# stoomshield1.net
KiCad netlist of a schematic drawn in EAGLE
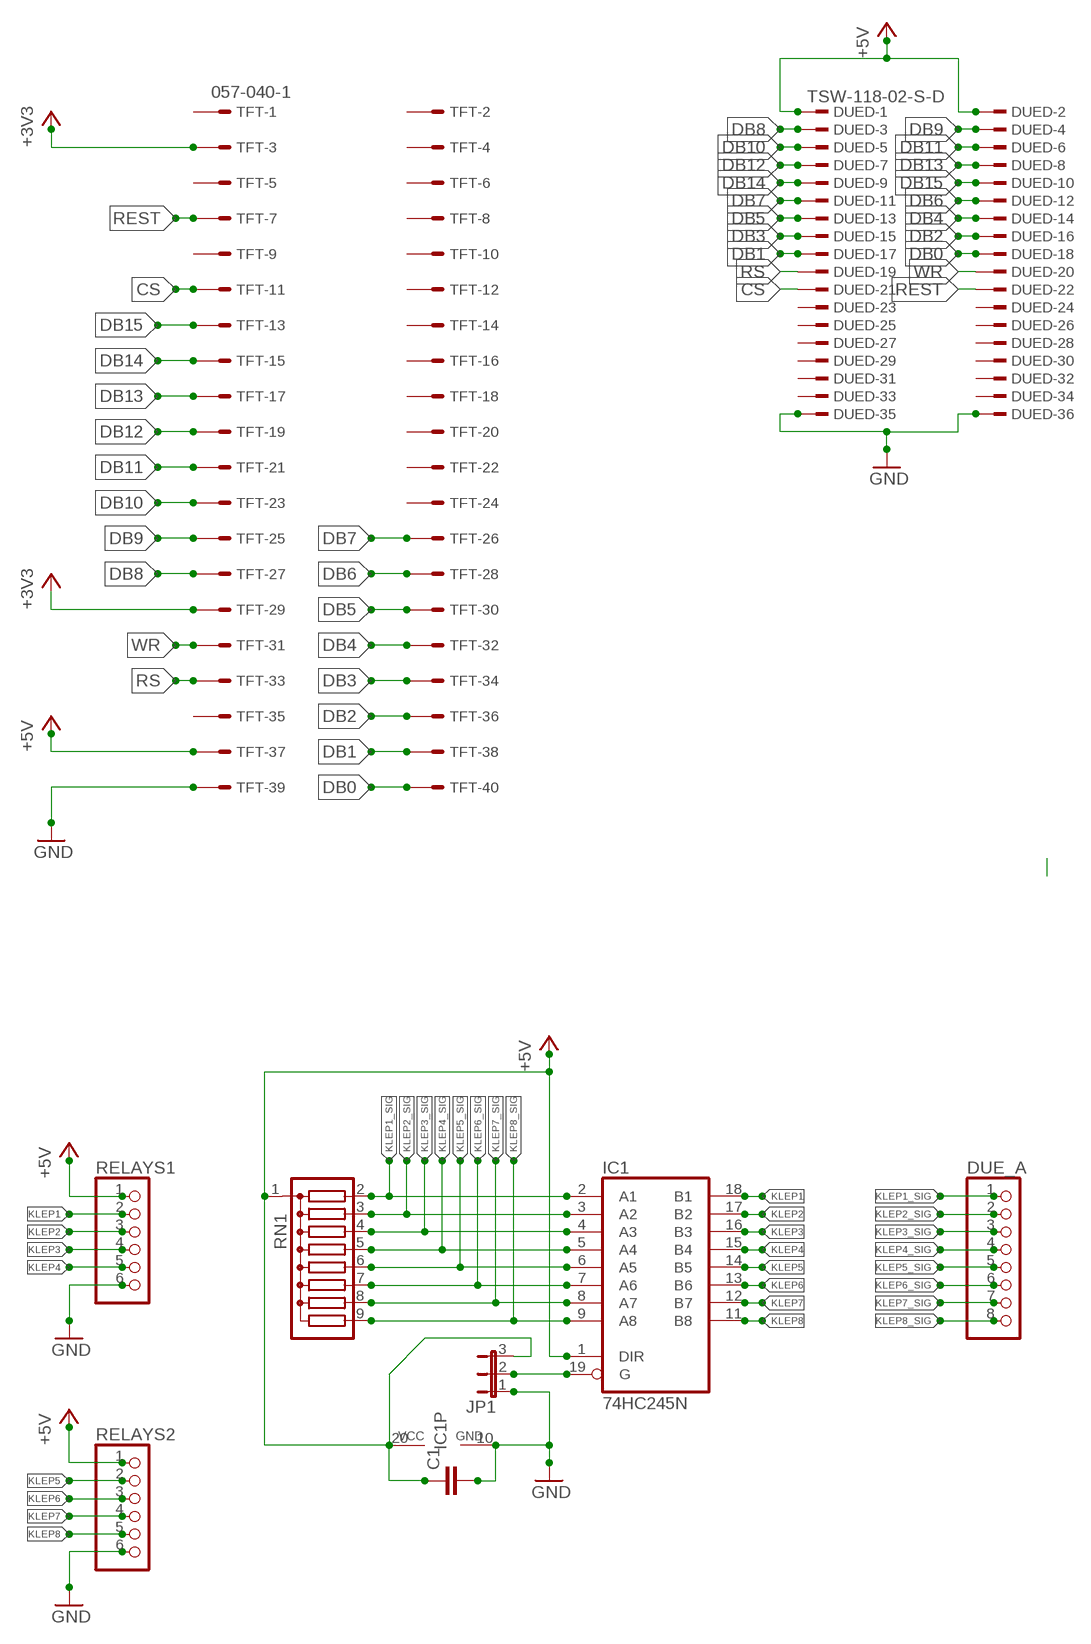
[diagram p0: schematic, sheet 1, part 1 of 2]
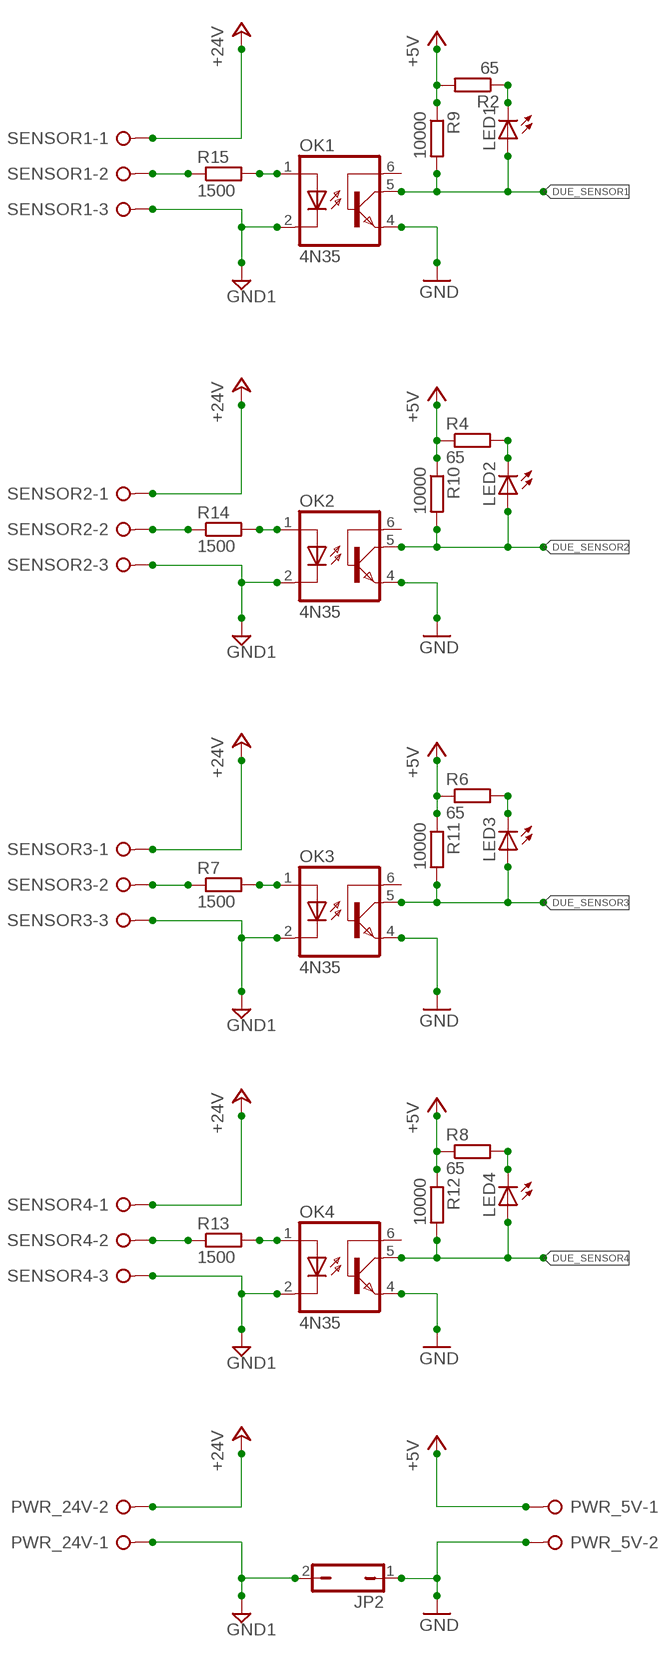
[diagram p1: schematic, sheet 1, part 2 of 2]

(export (version "E")
  (design (tool "Eeschema 10.0.6"))
  (components
    (comp (ref "C1")
      (value "C-EU025-024X044")
      (footprint "eagle-import:C025-024X044")
      (libsource (lib "eagle-import") (part "C-EU025-024X044"))
    )
    (comp (ref "DUED")
      (value "TSW-118-02-S-D")
      (footprint "eagle-import:TSW-118-02-S-D")
      (libsource (lib "eagle-import") (part "TSW-118-02-S-D"))
    )
    (comp (ref "DUE_A")
      (value "PINHD-1X8")
      (footprint "eagle-import:1X08")
      (libsource (lib "eagle-import") (part "PINHD-1X8"))
    )
    (comp (ref "IC1")
      (value "74HC245N")
      (footprint "eagle-import:DIL20")
      (libsource (lib "eagle-import") (part "74245NHC"))
    )
    (comp (ref "JP1")
      (value "JP2E")
      (footprint "eagle-import:JP2")
      (libsource (lib "eagle-import") (part "JP2E"))
    )
    (comp (ref "JP2")
      (value "JP1Q")
      (footprint "eagle-import:JP1")
      (libsource (lib "eagle-import") (part "JP1Q"))
    )
    (comp (ref "LED1")
      (value "LED5MM")
      (footprint "eagle-import:LED5MM")
      (libsource (lib "eagle-import") (part "LED5MM"))
    )
    (comp (ref "LED2")
      (value "LED5MM")
      (footprint "eagle-import:LED5MM")
      (libsource (lib "eagle-import") (part "LED5MM"))
    )
    (comp (ref "LED3")
      (value "LED5MM")
      (footprint "eagle-import:LED5MM")
      (libsource (lib "eagle-import") (part "LED5MM"))
    )
    (comp (ref "LED4")
      (value "LED5MM")
      (footprint "eagle-import:LED5MM")
      (libsource (lib "eagle-import") (part "LED5MM"))
    )
    (comp (ref "OK1")
      (value "4N35")
      (footprint "eagle-import:DIL06")
      (fields (field (name "MF") "FAIRCHILD SEMICONDUCTOR"))
      (libsource (lib "eagle-import") (part "4N35"))
    )
    (comp (ref "OK2")
      (value "4N35")
      (footprint "eagle-import:DIL06")
      (fields (field (name "MF") "FAIRCHILD SEMICONDUCTOR"))
      (libsource (lib "eagle-import") (part "4N35"))
    )
    (comp (ref "OK3")
      (value "4N35")
      (footprint "eagle-import:DIL06")
      (fields (field (name "MF") "FAIRCHILD SEMICONDUCTOR"))
      (libsource (lib "eagle-import") (part "4N35"))
    )
    (comp (ref "OK4")
      (value "4N35")
      (footprint "eagle-import:DIL06")
      (fields (field (name "MF") "FAIRCHILD SEMICONDUCTOR"))
      (libsource (lib "eagle-import") (part "4N35"))
    )
    (comp (ref "PWR_5V")
      (value "W237-02P")
      (footprint "eagle-import:W237-132")
      (libsource (lib "eagle-import") (part "W237-02P"))
    )
    (comp (ref "PWR_24V")
      (value "W237-02P")
      (footprint "eagle-import:W237-132")
      (libsource (lib "eagle-import") (part "W237-02P"))
    )
    (comp (ref "R2")
      (value "65")
      (footprint "eagle-import:0204_5")
      (libsource (lib "eagle-import") (part "R-EU_0204/5"))
    )
    (comp (ref "R4")
      (value "65")
      (footprint "eagle-import:0204_5")
      (libsource (lib "eagle-import") (part "R-EU_0204/5"))
    )
    (comp (ref "R6")
      (value "65")
      (footprint "eagle-import:0204_5")
      (libsource (lib "eagle-import") (part "R-EU_0204/5"))
    )
    (comp (ref "R7")
      (value "1500")
      (footprint "eagle-import:0204_5")
      (libsource (lib "eagle-import") (part "R-EU_0204/5"))
    )
    (comp (ref "R8")
      (value "65")
      (footprint "eagle-import:0204_5")
      (libsource (lib "eagle-import") (part "R-EU_0204/5"))
    )
    (comp (ref "R9")
      (value "10000")
      (footprint "eagle-import:0204_5")
      (libsource (lib "eagle-import") (part "R-EU_0204/5"))
    )
    (comp (ref "R10")
      (value "10000")
      (footprint "eagle-import:0204_5")
      (libsource (lib "eagle-import") (part "R-EU_0204/5"))
    )
    (comp (ref "R11")
      (value "10000")
      (footprint "eagle-import:0204_5")
      (libsource (lib "eagle-import") (part "R-EU_0204/5"))
    )
    (comp (ref "R12")
      (value "10000")
      (footprint "eagle-import:0204_5")
      (libsource (lib "eagle-import") (part "R-EU_0204/5"))
    )
    (comp (ref "R13")
      (value "1500")
      (footprint "eagle-import:0204_5")
      (libsource (lib "eagle-import") (part "R-EU_0204/5"))
    )
    (comp (ref "R14")
      (value "1500")
      (footprint "eagle-import:0204_5")
      (libsource (lib "eagle-import") (part "R-EU_0204/5"))
    )
    (comp (ref "R15")
      (value "1500")
      (footprint "eagle-import:0204_5")
      (libsource (lib "eagle-import") (part "R-EU_0204/5"))
    )
    (comp (ref "RELAYS1")
      (value "PINHD-1X6")
      (footprint "eagle-import:1X06")
      (libsource (lib "eagle-import") (part "PINHD-1X6"))
    )
    (comp (ref "RELAYS2")
      (value "PINHD-1X6")
      (footprint "eagle-import:1X06")
      (libsource (lib "eagle-import") (part "PINHD-1X6"))
    )
    (comp (ref "RN1")
      (value "G08R")
      (footprint "eagle-import:SIL9")
      (libsource (lib "eagle-import") (part "G08R"))
    )
    (comp (ref "SENSOR1")
      (value "W237-03P")
      (footprint "eagle-import:W237-133")
      (libsource (lib "eagle-import") (part "W237-03P"))
    )
    (comp (ref "SENSOR2")
      (value "W237-03P")
      (footprint "eagle-import:W237-133")
      (libsource (lib "eagle-import") (part "W237-03P"))
    )
    (comp (ref "SENSOR3")
      (value "W237-03P")
      (footprint "eagle-import:W237-133")
      (libsource (lib "eagle-import") (part "W237-03P"))
    )
    (comp (ref "SENSOR4")
      (value "W237-03P")
      (footprint "eagle-import:W237-133")
      (libsource (lib "eagle-import") (part "W237-03P"))
    )
    (comp (ref "TFT")
      (value "057-040-1")
      (footprint "eagle-import:057-040-1")
      (libsource (lib "eagle-import") (part "057-040-1"))
    )
  )
  (nets
    (net (code "1") (name "+3V3") (class "Default")
      (node (ref "TFT") (pin "29") (pinfunction "S_29") (pintype "passive"))
      (node (ref "TFT") (pin "3") (pinfunction "S_3") (pintype "passive"))
    )
    (net (code "2") (name "+5V") (class "Default")
      (node (ref "C1") (pin "1") (pinfunction "1_1") (pintype "passive"))
      (node (ref "DUED") (pin "1") (pinfunction "1_1") (pintype "passive"))
      (node (ref "DUED") (pin "2") (pinfunction "1_2") (pintype "passive"))
      (node (ref "IC1") (pin "1") (pinfunction "DIR_1") (pintype "input"))
      (node (ref "IC1") (pin "20") (pinfunction "VCC_20") (pintype "power_in"))
      (node (ref "JP1") (pin "3") (pinfunction "3_3") (pintype "passive"))
      (node (ref "PWR_5V") (pin "1") (pinfunction "KL_1") (pintype "passive"))
      (node (ref "R10") (pin "1") (pinfunction "1_1") (pintype "passive"))
      (node (ref "R11") (pin "1") (pinfunction "1_1") (pintype "passive"))
      (node (ref "R12") (pin "1") (pinfunction "1_1") (pintype "passive"))
      (node (ref "R2") (pin "2") (pinfunction "2_2") (pintype "passive"))
      (node (ref "R4") (pin "1") (pinfunction "1_1") (pintype "passive"))
      (node (ref "R6") (pin "1") (pinfunction "1_1") (pintype "passive"))
      (node (ref "R8") (pin "1") (pinfunction "1_1") (pintype "passive"))
      (node (ref "R9") (pin "1") (pinfunction "1_1") (pintype "passive"))
      (node (ref "RELAYS1") (pin "1") (pinfunction "1_1") (pintype "passive"))
      (node (ref "RELAYS2") (pin "1") (pinfunction "1_1") (pintype "passive"))
      (node (ref "RN1") (pin "1") (pinfunction "1_1") (pintype "passive"))
      (node (ref "TFT") (pin "37") (pinfunction "S_37") (pintype "passive"))
    )
    (net (code "3") (name "+24V") (class "Default")
      (node (ref "PWR_24V") (pin "2") (pinfunction "KL_2") (pintype "passive"))
      (node (ref "SENSOR1") (pin "1") (pinfunction "KL_1") (pintype "passive"))
      (node (ref "SENSOR2") (pin "1") (pinfunction "KL_1") (pintype "passive"))
      (node (ref "SENSOR3") (pin "1") (pinfunction "KL_1") (pintype "passive"))
      (node (ref "SENSOR4") (pin "1") (pinfunction "KL_1") (pintype "passive"))
    )
    (net (code "4") (name "CS") (class "Default")
      (node (ref "DUED") (pin "21") (pinfunction "1_21") (pintype "passive"))
      (node (ref "TFT") (pin "11") (pinfunction "S_11") (pintype "passive"))
    )
    (net (code "5") (name "DB0") (class "Default")
      (node (ref "DUED") (pin "18") (pinfunction "1_18") (pintype "passive"))
      (node (ref "TFT") (pin "40") (pinfunction "S_40") (pintype "passive"))
    )
    (net (code "6") (name "DB1") (class "Default")
      (node (ref "DUED") (pin "17") (pinfunction "1_17") (pintype "passive"))
      (node (ref "TFT") (pin "38") (pinfunction "S_38") (pintype "passive"))
    )
    (net (code "7") (name "DB2") (class "Default")
      (node (ref "DUED") (pin "16") (pinfunction "1_16") (pintype "passive"))
      (node (ref "TFT") (pin "36") (pinfunction "S_36") (pintype "passive"))
    )
    (net (code "8") (name "DB3") (class "Default")
      (node (ref "DUED") (pin "15") (pinfunction "1_15") (pintype "passive"))
      (node (ref "TFT") (pin "34") (pinfunction "S_34") (pintype "passive"))
    )
    (net (code "9") (name "DB4") (class "Default")
      (node (ref "DUED") (pin "14") (pinfunction "1_14") (pintype "passive"))
      (node (ref "TFT") (pin "32") (pinfunction "S_32") (pintype "passive"))
    )
    (net (code "10") (name "DB5") (class "Default")
      (node (ref "DUED") (pin "13") (pinfunction "1_13") (pintype "passive"))
      (node (ref "TFT") (pin "30") (pinfunction "S_30") (pintype "passive"))
    )
    (net (code "11") (name "DB6") (class "Default")
      (node (ref "DUED") (pin "12") (pinfunction "1_12") (pintype "passive"))
      (node (ref "TFT") (pin "28") (pinfunction "S_28") (pintype "passive"))
    )
    (net (code "12") (name "DB7") (class "Default")
      (node (ref "DUED") (pin "11") (pinfunction "1_11") (pintype "passive"))
      (node (ref "TFT") (pin "26") (pinfunction "S_26") (pintype "passive"))
    )
    (net (code "13") (name "DB8") (class "Default")
      (node (ref "DUED") (pin "3") (pinfunction "1_3") (pintype "passive"))
      (node (ref "TFT") (pin "27") (pinfunction "S_27") (pintype "passive"))
    )
    (net (code "14") (name "DB9") (class "Default")
      (node (ref "DUED") (pin "4") (pinfunction "1_4") (pintype "passive"))
      (node (ref "TFT") (pin "25") (pinfunction "S_25") (pintype "passive"))
    )
    (net (code "15") (name "DB10") (class "Default")
      (node (ref "DUED") (pin "5") (pinfunction "1_5") (pintype "passive"))
      (node (ref "TFT") (pin "23") (pinfunction "S_23") (pintype "passive"))
    )
    (net (code "16") (name "DB11") (class "Default")
      (node (ref "DUED") (pin "6") (pinfunction "1_6") (pintype "passive"))
      (node (ref "TFT") (pin "21") (pinfunction "S_21") (pintype "passive"))
    )
    (net (code "17") (name "DB12") (class "Default")
      (node (ref "DUED") (pin "7") (pinfunction "1_7") (pintype "passive"))
      (node (ref "TFT") (pin "19") (pinfunction "S_19") (pintype "passive"))
    )
    (net (code "18") (name "DB13") (class "Default")
      (node (ref "DUED") (pin "8") (pinfunction "1_8") (pintype "passive"))
      (node (ref "TFT") (pin "17") (pinfunction "S_17") (pintype "passive"))
    )
    (net (code "19") (name "DB14") (class "Default")
      (node (ref "DUED") (pin "9") (pinfunction "1_9") (pintype "passive"))
      (node (ref "TFT") (pin "15") (pinfunction "S_15") (pintype "passive"))
    )
    (net (code "20") (name "DB15") (class "Default")
      (node (ref "DUED") (pin "10") (pinfunction "1_10") (pintype "passive"))
      (node (ref "TFT") (pin "13") (pinfunction "S_13") (pintype "passive"))
    )
    (net (code "21") (name "DUE_SENSOR1") (class "Default")
      (node (ref "LED1") (pin "A") (pinfunction "A_A") (pintype "passive"))
      (node (ref "OK1") (pin "5") (pinfunction "COL_5") (pintype "passive"))
      (node (ref "R9") (pin "2") (pinfunction "2_2") (pintype "passive"))
    )
    (net (code "22") (name "DUE_SENSOR2") (class "Default")
      (node (ref "LED2") (pin "A") (pinfunction "A_A") (pintype "passive"))
      (node (ref "OK2") (pin "5") (pinfunction "COL_5") (pintype "passive"))
      (node (ref "R10") (pin "2") (pinfunction "2_2") (pintype "passive"))
    )
    (net (code "23") (name "DUE_SENSOR3") (class "Default")
      (node (ref "LED3") (pin "A") (pinfunction "A_A") (pintype "passive"))
      (node (ref "OK3") (pin "5") (pinfunction "COL_5") (pintype "passive"))
      (node (ref "R11") (pin "2") (pinfunction "2_2") (pintype "passive"))
    )
    (net (code "24") (name "DUE_SENSOR4") (class "Default")
      (node (ref "LED4") (pin "A") (pinfunction "A_A") (pintype "passive"))
      (node (ref "OK4") (pin "5") (pinfunction "COL_5") (pintype "passive"))
      (node (ref "R12") (pin "2") (pinfunction "2_2") (pintype "passive"))
    )
    (net (code "25") (name "GND") (class "Default")
      (node (ref "C1") (pin "2") (pinfunction "2_2") (pintype "passive"))
      (node (ref "DUED") (pin "35") (pinfunction "1_35") (pintype "passive"))
      (node (ref "DUED") (pin "36") (pinfunction "1_36") (pintype "passive"))
      (node (ref "IC1") (pin "10") (pinfunction "GND_10") (pintype "power_in"))
      (node (ref "JP1") (pin "1") (pinfunction "1_1") (pintype "passive"))
      (node (ref "JP2") (pin "1") (pinfunction "1_1") (pintype "passive"))
      (node (ref "OK1") (pin "4") (pinfunction "EMI_4") (pintype "passive"))
      (node (ref "OK2") (pin "4") (pinfunction "EMI_4") (pintype "passive"))
      (node (ref "OK3") (pin "4") (pinfunction "EMI_4") (pintype "passive"))
      (node (ref "OK4") (pin "4") (pinfunction "EMI_4") (pintype "passive"))
      (node (ref "PWR_5V") (pin "2") (pinfunction "KL_2") (pintype "passive"))
      (node (ref "RELAYS1") (pin "6") (pinfunction "6_6") (pintype "passive"))
      (node (ref "RELAYS2") (pin "6") (pinfunction "6_6") (pintype "passive"))
      (node (ref "TFT") (pin "39") (pinfunction "S_39") (pintype "passive"))
    )
    (net (code "26") (name "GND1") (class "Default")
      (node (ref "JP2") (pin "2") (pinfunction "2_2") (pintype "passive"))
      (node (ref "OK1") (pin "2") (pinfunction "C_2") (pintype "passive"))
      (node (ref "OK2") (pin "2") (pinfunction "C_2") (pintype "passive"))
      (node (ref "OK3") (pin "2") (pinfunction "C_2") (pintype "passive"))
      (node (ref "OK4") (pin "2") (pinfunction "C_2") (pintype "passive"))
      (node (ref "PWR_24V") (pin "1") (pinfunction "KL_1") (pintype "passive"))
      (node (ref "SENSOR1") (pin "3") (pinfunction "KL_3") (pintype "passive"))
      (node (ref "SENSOR2") (pin "3") (pinfunction "KL_3") (pintype "passive"))
      (node (ref "SENSOR3") (pin "3") (pinfunction "KL_3") (pintype "passive"))
      (node (ref "SENSOR4") (pin "3") (pinfunction "KL_3") (pintype "passive"))
    )
    (net (code "27") (name "KLEP1") (class "Default")
      (node (ref "IC1") (pin "18") (pinfunction "B1_18") (pintype "bidirectional"))
      (node (ref "RELAYS1") (pin "2") (pinfunction "2_2") (pintype "passive"))
    )
    (net (code "28") (name "KLEP1_SIG") (class "Default")
      (node (ref "DUE_A") (pin "1") (pinfunction "1_1") (pintype "passive"))
      (node (ref "IC1") (pin "2") (pinfunction "A1_2") (pintype "bidirectional"))
      (node (ref "RN1") (pin "2") (pinfunction "2_2") (pintype "passive"))
    )
    (net (code "29") (name "KLEP2") (class "Default")
      (node (ref "IC1") (pin "17") (pinfunction "B2_17") (pintype "bidirectional"))
      (node (ref "RELAYS1") (pin "3") (pinfunction "3_3") (pintype "passive"))
    )
    (net (code "30") (name "KLEP2_SIG") (class "Default")
      (node (ref "DUE_A") (pin "2") (pinfunction "2_2") (pintype "passive"))
      (node (ref "IC1") (pin "3") (pinfunction "A2_3") (pintype "bidirectional"))
      (node (ref "RN1") (pin "3") (pinfunction "3_3") (pintype "passive"))
    )
    (net (code "31") (name "KLEP3") (class "Default")
      (node (ref "IC1") (pin "16") (pinfunction "B3_16") (pintype "bidirectional"))
      (node (ref "RELAYS1") (pin "4") (pinfunction "4_4") (pintype "passive"))
    )
    (net (code "32") (name "KLEP3_SIG") (class "Default")
      (node (ref "DUE_A") (pin "3") (pinfunction "3_3") (pintype "passive"))
      (node (ref "IC1") (pin "4") (pinfunction "A3_4") (pintype "bidirectional"))
      (node (ref "RN1") (pin "4") (pinfunction "4_4") (pintype "passive"))
    )
    (net (code "33") (name "KLEP4") (class "Default")
      (node (ref "IC1") (pin "15") (pinfunction "B4_15") (pintype "bidirectional"))
      (node (ref "RELAYS1") (pin "5") (pinfunction "5_5") (pintype "passive"))
    )
    (net (code "34") (name "KLEP4_SIG") (class "Default")
      (node (ref "DUE_A") (pin "4") (pinfunction "4_4") (pintype "passive"))
      (node (ref "IC1") (pin "5") (pinfunction "A4_5") (pintype "bidirectional"))
      (node (ref "RN1") (pin "5") (pinfunction "5_5") (pintype "passive"))
    )
    (net (code "35") (name "KLEP5") (class "Default")
      (node (ref "IC1") (pin "14") (pinfunction "B5_14") (pintype "bidirectional"))
      (node (ref "RELAYS2") (pin "2") (pinfunction "2_2") (pintype "passive"))
    )
    (net (code "36") (name "KLEP5_SIG") (class "Default")
      (node (ref "DUE_A") (pin "5") (pinfunction "5_5") (pintype "passive"))
      (node (ref "IC1") (pin "6") (pinfunction "A5_6") (pintype "bidirectional"))
      (node (ref "RN1") (pin "6") (pinfunction "6_6") (pintype "passive"))
    )
    (net (code "37") (name "KLEP6") (class "Default")
      (node (ref "IC1") (pin "13") (pinfunction "B6_13") (pintype "bidirectional"))
      (node (ref "RELAYS2") (pin "3") (pinfunction "3_3") (pintype "passive"))
    )
    (net (code "38") (name "KLEP6_SIG") (class "Default")
      (node (ref "DUE_A") (pin "6") (pinfunction "6_6") (pintype "passive"))
      (node (ref "IC1") (pin "7") (pinfunction "A6_7") (pintype "bidirectional"))
      (node (ref "RN1") (pin "7") (pinfunction "7_7") (pintype "passive"))
    )
    (net (code "39") (name "KLEP7") (class "Default")
      (node (ref "IC1") (pin "12") (pinfunction "B7_12") (pintype "bidirectional"))
      (node (ref "RELAYS2") (pin "4") (pinfunction "4_4") (pintype "passive"))
    )
    (net (code "40") (name "KLEP7_SIG") (class "Default")
      (node (ref "DUE_A") (pin "7") (pinfunction "7_7") (pintype "passive"))
      (node (ref "IC1") (pin "8") (pinfunction "A7_8") (pintype "bidirectional"))
      (node (ref "RN1") (pin "8") (pinfunction "8_8") (pintype "passive"))
    )
    (net (code "41") (name "KLEP8") (class "Default")
      (node (ref "IC1") (pin "11") (pinfunction "B8_11") (pintype "bidirectional"))
      (node (ref "RELAYS2") (pin "5") (pinfunction "5_5") (pintype "passive"))
    )
    (net (code "42") (name "KLEP8_SIG") (class "Default")
      (node (ref "DUE_A") (pin "8") (pinfunction "8_8") (pintype "passive"))
      (node (ref "IC1") (pin "9") (pinfunction "A8_9") (pintype "bidirectional"))
      (node (ref "RN1") (pin "9") (pinfunction "9_9") (pintype "passive"))
    )
    (net (code "43") (name "Net-(IC1A-G)") (class "Default")
      (node (ref "IC1") (pin "19") (pinfunction "G_19") (pintype "input"))
      (node (ref "JP1") (pin "2") (pinfunction "2_2") (pintype "passive"))
    )
    (net (code "44") (name "Net-(LED1-C)") (class "Default")
      (node (ref "LED1") (pin "K") (pinfunction "C_K") (pintype "passive"))
      (node (ref "R2") (pin "1") (pinfunction "1_1") (pintype "passive"))
    )
    (net (code "45") (name "Net-(LED2-C)") (class "Default")
      (node (ref "LED2") (pin "K") (pinfunction "C_K") (pintype "passive"))
      (node (ref "R4") (pin "2") (pinfunction "2_2") (pintype "passive"))
    )
    (net (code "46") (name "Net-(LED3-C)") (class "Default")
      (node (ref "LED3") (pin "K") (pinfunction "C_K") (pintype "passive"))
      (node (ref "R6") (pin "2") (pinfunction "2_2") (pintype "passive"))
    )
    (net (code "47") (name "Net-(LED4-C)") (class "Default")
      (node (ref "LED4") (pin "K") (pinfunction "C_K") (pintype "passive"))
      (node (ref "R8") (pin "2") (pinfunction "2_2") (pintype "passive"))
    )
    (net (code "48") (name "Net-(OK1-A)") (class "Default")
      (node (ref "OK1") (pin "1") (pinfunction "A_1") (pintype "passive"))
      (node (ref "R15") (pin "2") (pinfunction "2_2") (pintype "passive"))
    )
    (net (code "49") (name "Net-(OK2-A)") (class "Default")
      (node (ref "OK2") (pin "1") (pinfunction "A_1") (pintype "passive"))
      (node (ref "R14") (pin "2") (pinfunction "2_2") (pintype "passive"))
    )
    (net (code "50") (name "Net-(OK3-A)") (class "Default")
      (node (ref "OK3") (pin "1") (pinfunction "A_1") (pintype "passive"))
      (node (ref "R7") (pin "2") (pinfunction "2_2") (pintype "passive"))
    )
    (net (code "51") (name "Net-(OK4-A)") (class "Default")
      (node (ref "OK4") (pin "1") (pinfunction "A_1") (pintype "passive"))
      (node (ref "R13") (pin "2") (pinfunction "2_2") (pintype "passive"))
    )
    (net (code "52") (name "Net-(SENSOR1B-KL)") (class "Default")
      (node (ref "R15") (pin "1") (pinfunction "1_1") (pintype "passive"))
      (node (ref "SENSOR1") (pin "2") (pinfunction "KL_2") (pintype "passive"))
    )
    (net (code "53") (name "Net-(SENSOR2B-KL)") (class "Default")
      (node (ref "R14") (pin "1") (pinfunction "1_1") (pintype "passive"))
      (node (ref "SENSOR2") (pin "2") (pinfunction "KL_2") (pintype "passive"))
    )
    (net (code "54") (name "Net-(SENSOR3B-KL)") (class "Default")
      (node (ref "R7") (pin "1") (pinfunction "1_1") (pintype "passive"))
      (node (ref "SENSOR3") (pin "2") (pinfunction "KL_2") (pintype "passive"))
    )
    (net (code "55") (name "Net-(SENSOR4B-KL)") (class "Default")
      (node (ref "R13") (pin "1") (pinfunction "1_1") (pintype "passive"))
      (node (ref "SENSOR4") (pin "2") (pinfunction "KL_2") (pintype "passive"))
    )
    (net (code "56") (name "REST") (class "Default")
      (node (ref "DUED") (pin "22") (pinfunction "1_22") (pintype "passive"))
      (node (ref "TFT") (pin "7") (pinfunction "S_7") (pintype "passive"))
    )
    (net (code "57") (name "RS") (class "Default")
      (node (ref "DUED") (pin "19") (pinfunction "1_19") (pintype "passive"))
      (node (ref "TFT") (pin "33") (pinfunction "S_33") (pintype "passive"))
    )
    (net (code "58") (name "WR") (class "Default")
      (node (ref "DUED") (pin "20") (pinfunction "1_20") (pintype "passive"))
      (node (ref "TFT") (pin "31") (pinfunction "S_31") (pintype "passive"))
    )
    (net (code "59") (name "unconnected-(DUEDAA-1-Pad33)") (class "Default")
      (node (ref "DUED") (pin "33") (pinfunction "1_33") (pintype "passive"))
    )
    (net (code "60") (name "unconnected-(DUEDAB-1-Pad34)") (class "Default")
      (node (ref "DUED") (pin "34") (pinfunction "1_34") (pintype "passive"))
    )
    (net (code "61") (name "unconnected-(DUEDP-1-Pad23)") (class "Default")
      (node (ref "DUED") (pin "23") (pinfunction "1_23") (pintype "passive"))
    )
    (net (code "62") (name "unconnected-(DUEDQ-1-Pad24)") (class "Default")
      (node (ref "DUED") (pin "24") (pinfunction "1_24") (pintype "passive"))
    )
    (net (code "63") (name "unconnected-(DUEDR-1-Pad25)") (class "Default")
      (node (ref "DUED") (pin "25") (pinfunction "1_25") (pintype "passive"))
    )
    (net (code "64") (name "unconnected-(DUEDS-1-Pad26)") (class "Default")
      (node (ref "DUED") (pin "26") (pinfunction "1_26") (pintype "passive"))
    )
    (net (code "65") (name "unconnected-(DUEDT-1-Pad27)") (class "Default")
      (node (ref "DUED") (pin "27") (pinfunction "1_27") (pintype "passive"))
    )
    (net (code "66") (name "unconnected-(DUEDU-1-Pad28)") (class "Default")
      (node (ref "DUED") (pin "28") (pinfunction "1_28") (pintype "passive"))
    )
    (net (code "67") (name "unconnected-(DUEDV-1-Pad29)") (class "Default")
      (node (ref "DUED") (pin "29") (pinfunction "1_29") (pintype "passive"))
    )
    (net (code "68") (name "unconnected-(DUEDX-1-Pad30)") (class "Default")
      (node (ref "DUED") (pin "30") (pinfunction "1_30") (pintype "passive"))
    )
    (net (code "69") (name "unconnected-(DUEDY-1-Pad31)") (class "Default")
      (node (ref "DUED") (pin "31") (pinfunction "1_31") (pintype "passive"))
    )
    (net (code "70") (name "unconnected-(DUEDZ-1-Pad32)") (class "Default")
      (node (ref "DUED") (pin "32") (pinfunction "1_32") (pintype "passive"))
    )
    (net (code "71") (name "unconnected-(OK1-BAS-Pad6)") (class "Default")
      (node (ref "OK1") (pin "6") (pinfunction "BAS_6") (pintype "passive"))
    )
    (net (code "72") (name "unconnected-(OK2-BAS-Pad6)") (class "Default")
      (node (ref "OK2") (pin "6") (pinfunction "BAS_6") (pintype "passive"))
    )
    (net (code "73") (name "unconnected-(OK3-BAS-Pad6)") (class "Default")
      (node (ref "OK3") (pin "6") (pinfunction "BAS_6") (pintype "passive"))
    )
    (net (code "74") (name "unconnected-(OK4-BAS-Pad6)") (class "Default")
      (node (ref "OK4") (pin "6") (pinfunction "BAS_6") (pintype "passive"))
    )
    (net (code "75") (name "unconnected-(TFTA-S-Pad1)") (class "Default")
      (node (ref "TFT") (pin "1") (pinfunction "S_1") (pintype "passive"))
    )
    (net (code "76") (name "unconnected-(TFTAC-S-Pad35)") (class "Default")
      (node (ref "TFT") (pin "35") (pinfunction "S_35") (pintype "passive"))
    )
    (net (code "77") (name "unconnected-(TFTAH-S-Pad4)") (class "Default")
      (node (ref "TFT") (pin "4") (pinfunction "S_4") (pintype "passive"))
    )
    (net (code "78") (name "unconnected-(TFTAJ-S-Pad5)") (class "Default")
      (node (ref "TFT") (pin "5") (pinfunction "S_5") (pintype "passive"))
    )
    (net (code "79") (name "unconnected-(TFTAK-S-Pad6)") (class "Default")
      (node (ref "TFT") (pin "6") (pinfunction "S_6") (pintype "passive"))
    )
    (net (code "80") (name "unconnected-(TFTAM-S-Pad8)") (class "Default")
      (node (ref "TFT") (pin "8") (pinfunction "S_8") (pintype "passive"))
    )
    (net (code "81") (name "unconnected-(TFTAN-S-Pad9)") (class "Default")
      (node (ref "TFT") (pin "9") (pinfunction "S_9") (pintype "passive"))
    )
    (net (code "82") (name "unconnected-(TFTB-S-Pad10)") (class "Default")
      (node (ref "TFT") (pin "10") (pinfunction "S_10") (pintype "passive"))
    )
    (net (code "83") (name "unconnected-(TFTD-S-Pad12)") (class "Default")
      (node (ref "TFT") (pin "12") (pinfunction "S_12") (pintype "passive"))
    )
    (net (code "84") (name "unconnected-(TFTF-S-Pad14)") (class "Default")
      (node (ref "TFT") (pin "14") (pinfunction "S_14") (pintype "passive"))
    )
    (net (code "85") (name "unconnected-(TFTH-S-Pad16)") (class "Default")
      (node (ref "TFT") (pin "16") (pinfunction "S_16") (pintype "passive"))
    )
    (net (code "86") (name "unconnected-(TFTJ-S-Pad18)") (class "Default")
      (node (ref "TFT") (pin "18") (pinfunction "S_18") (pintype "passive"))
    )
    (net (code "87") (name "unconnected-(TFTL-S-Pad2)") (class "Default")
      (node (ref "TFT") (pin "2") (pinfunction "S_2") (pintype "passive"))
    )
    (net (code "88") (name "unconnected-(TFTM-S-Pad20)") (class "Default")
      (node (ref "TFT") (pin "20") (pinfunction "S_20") (pintype "passive"))
    )
    (net (code "89") (name "unconnected-(TFTO-S-Pad22)") (class "Default")
      (node (ref "TFT") (pin "22") (pinfunction "S_22") (pintype "passive"))
    )
    (net (code "90") (name "unconnected-(TFTQ-S-Pad24)") (class "Default")
      (node (ref "TFT") (pin "24") (pinfunction "S_24") (pintype "passive"))
    )
  )
)
